# Rtc.net
KiCad netlist of a schematic drawn in Altium Designer
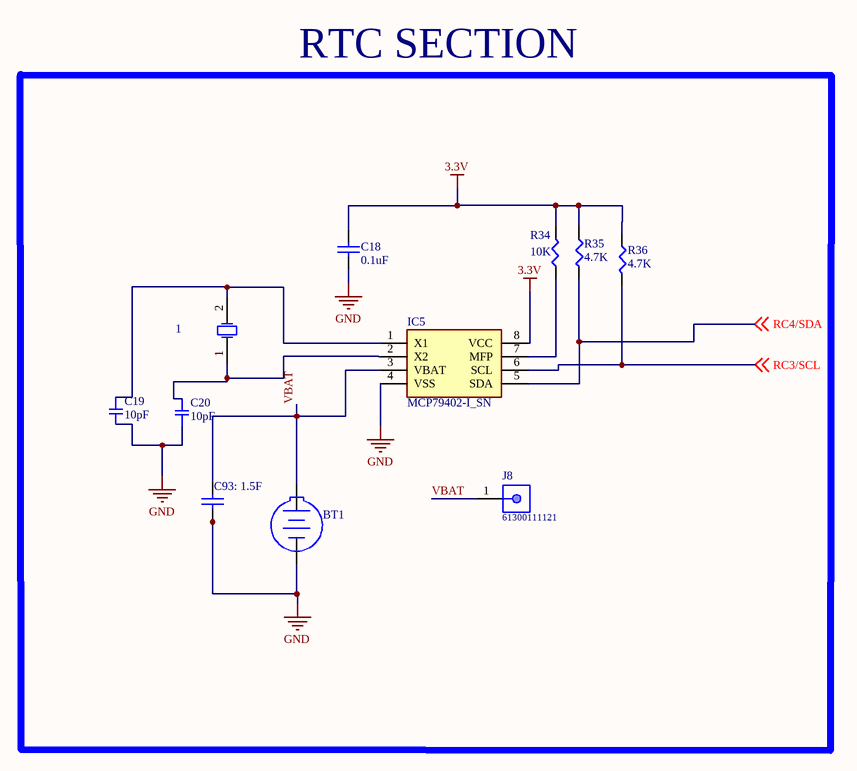
[diagram p0: Rtc.SchDoc]

(export (version "E")
  (design (tool "Eeschema 10.0.6"))
  (components
    (comp (ref "1")
      (value "~")
      (footprint "Mini Crystal")
      (description "9B-64.000MBBK-B")
      (fields (field (name "MANUFACTURER") "Abracon") (field (name "PARTNUMBER") "ABLS2-4.096MHZ-D4Y-T"))
      (libsource (lib "Medi Custom library") (part "Mini Crystal"))
    )
    (comp (ref "BT1")
      (value "79578211")
      (footprint "79578211")
      (description "WA-BCPH Battery Holder, THT, battery type 2450")
      (fields (field (name "MANUFACTURER") "Wurth Elektronik"))
      (libsource (lib "Battery Holders") (part "79578211"))
    )
    (comp (ref "C18")
      (value "0.1uF")
      (footprint "C1206")
      (description "Capacitor (Semiconductor SIM Model)")
      (fields (field (name "Comment") "Cap Semi") (field (name "PUBLISHER") "Altium Limited"))
      (libsource (lib "Miscellaneous Devices") (part "Cap Semi"))
    )
    (comp (ref "C19")
      (value "10pF")
      (footprint "SMD-0805C")
      (description "CAP CER 0.1UF 50V X7R 0805")
      (fields
        (field (name "DIGI-KEY PART NUMBER") "490-11955-1-ND")
        (field (name "PART NUMBER") "GCD21BR71H104KA01L")
      )
      (libsource (lib "capacitor_murata_0805") (part "GCD21BR71H104KA01L"))
    )
    (comp (ref "C20")
      (value "10pF")
      (footprint "SMD-0805C")
      (description "CAP CER 0.1UF 50V X7R 0805")
      (fields
        (field (name "DIGI-KEY PART NUMBER") "490-11955-1-ND")
        (field (name "PART NUMBER") "GCD21BR71H104KA01L")
      )
      (libsource (lib "capacitor_murata_0805") (part "GCD21BR71H104KA01L"))
    )
    (comp (ref "IC5")
      (value "MCP79402-I_SN")
      (footprint "SamacSys:SOIC127P600X175-8N")
      (description "Integrated Circuit")
      (fields
        (field (name "MANUFACTURER_PART_NUMBER") "MCP79402-I/SN")
        (field (name "MOUSER PART NUMBER") "579-MCP79402ISN")
      )
      (libsource (lib "*") (part "MCP79402-I_SN"))
    )
    (comp (ref "J8")
      (value "61300111121")
      (footprint "61300111121")
      (description "WR-PHD Pin Header, THT, pitch 2.54mm, Single Row, Vertical, 1pin")
      (fields (field (name "PUBLISHER") "Wurth Elektronik"))
      (libsource (lib "SIL_Connectors WR-PHD_rev19a") (part "61300111121"))
    )
    (comp (ref "R34")
      (value "10K")
      (footprint "SMD-0805-RES")
      (description "RES SMD 1K OHM 1% 1/8W 0805")
      (fields
        (field (name "PART NUMBER") "ERJ-6ENF1001V")
        (field (name "DIGI-KEY PART NUMBER") "P1.00KCCT-ND")
      )
      (libsource (lib "Panasonic_ERJ_0805") (part "ERJ-6ENF1001V"))
    )
    (comp (ref "R35")
      (value "4.7K")
      (footprint "SMD-0805-RES")
      (description "RES SMD 1K OHM 1% 1/8W 0805")
      (fields
        (field (name "PART NUMBER") "ERJ-6ENF1001V")
        (field (name "DIGI-KEY PART NUMBER") "P1.00KCCT-ND")
      )
      (libsource (lib "Panasonic_ERJ_0805") (part "ERJ-6ENF1001V"))
    )
    (comp (ref "R36")
      (value "4.7K")
      (footprint "SMD-0805-RES")
      (description "RES SMD 1K OHM 1% 1/8W 0805")
      (fields
        (field (name "PART NUMBER") "ERJ-6ENF1001V")
        (field (name "DIGI-KEY PART NUMBER") "P1.00KCCT-ND")
      )
      (libsource (lib "Panasonic_ERJ_0805") (part "ERJ-6ENF1001V"))
    )
    (comp (ref "SuperCap1")
      (value "Cap Semi")
      (footprint "C1206")
      (description "Capacitor (Semiconductor SIM Model)")
      (fields (field (name "C93") "1.5F") (field (name "PUBLISHER") "Altium Limited"))
      (libsource (lib "Miscellaneous Devices") (part "Cap Semi"))
    )
  )
  (nets
    (net (code "2") (name "/VBAT") (class "Default")
      (node (ref "BT1") (pin "1") (pinfunction "+_1") (pintype "passive"))
      (node (ref "IC5") (pin "3") (pinfunction "VBAT_3") (pintype "passive"))
      (node (ref "J8") (pin "1") (pinfunction "1_1") (pintype "passive"))
      (node (ref "SuperCap1") (pin "1") (pinfunction "1_1") (pintype "passive"))
    )
    (net (code "3") (name "3.3V") (class "Default")
      (node (ref "C18") (pin "1") (pinfunction "1_1") (pintype "passive"))
      (node (ref "IC5") (pin "8") (pinfunction "VCC_8") (pintype "passive"))
      (node (ref "R34") (pin "2") (pinfunction "2_2") (pintype "passive"))
      (node (ref "R35") (pin "1") (pinfunction "1_1") (pintype "passive"))
      (node (ref "R36") (pin "1") (pinfunction "1_1") (pintype "passive"))
    )
    (net (code "4") (name "GND") (class "Default")
      (node (ref "BT1") (pin "2") (pinfunction "-_2") (pintype "passive"))
      (node (ref "C18") (pin "2") (pinfunction "2_2") (pintype "passive"))
      (node (ref "C19") (pin "2") (pinfunction "2_2") (pintype "passive"))
      (node (ref "C20") (pin "2") (pinfunction "2_2") (pintype "passive"))
      (node (ref "IC5") (pin "4") (pinfunction "VSS_4") (pintype "passive"))
      (node (ref "SuperCap1") (pin "2") (pinfunction "2_2") (pintype "passive"))
    )
    (net (code "5") (name "Net-(1-X1)") (class "Default")
      (node (ref "1") (pin "1") (pinfunction "X1_1") (pintype "passive"))
      (node (ref "C20") (pin "1") (pinfunction "1_1") (pintype "passive"))
      (node (ref "IC5") (pin "2") (pinfunction "X2_2") (pintype "passive"))
    )
    (net (code "6") (name "Net-(1-X2)") (class "Default")
      (node (ref "1") (pin "2") (pinfunction "X2_2") (pintype "passive"))
      (node (ref "C19") (pin "1") (pinfunction "1_1") (pintype "passive"))
      (node (ref "IC5") (pin "1") (pinfunction "X1_1") (pintype "passive"))
    )
    (net (code "7") (name "Net-(IC5-MFP)") (class "Default")
      (node (ref "IC5") (pin "7") (pinfunction "MFP_7") (pintype "passive"))
      (node (ref "R34") (pin "1") (pinfunction "1_1") (pintype "passive"))
    )
    (net (code "8") (name "RC3{slash}SCL") (class "Default")
      (node (ref "IC5") (pin "6") (pinfunction "SCL_6") (pintype "passive"))
      (node (ref "R36") (pin "2") (pinfunction "2_2") (pintype "passive"))
    )
    (net (code "9") (name "RC4{slash}SDA") (class "Default")
      (node (ref "IC5") (pin "5") (pinfunction "SDA_5") (pintype "passive"))
      (node (ref "R35") (pin "2") (pinfunction "2_2") (pintype "passive"))
    )
  )
)
